# jit_pcb_smd.net
KiCad netlist of a schematic drawn in EAGLE
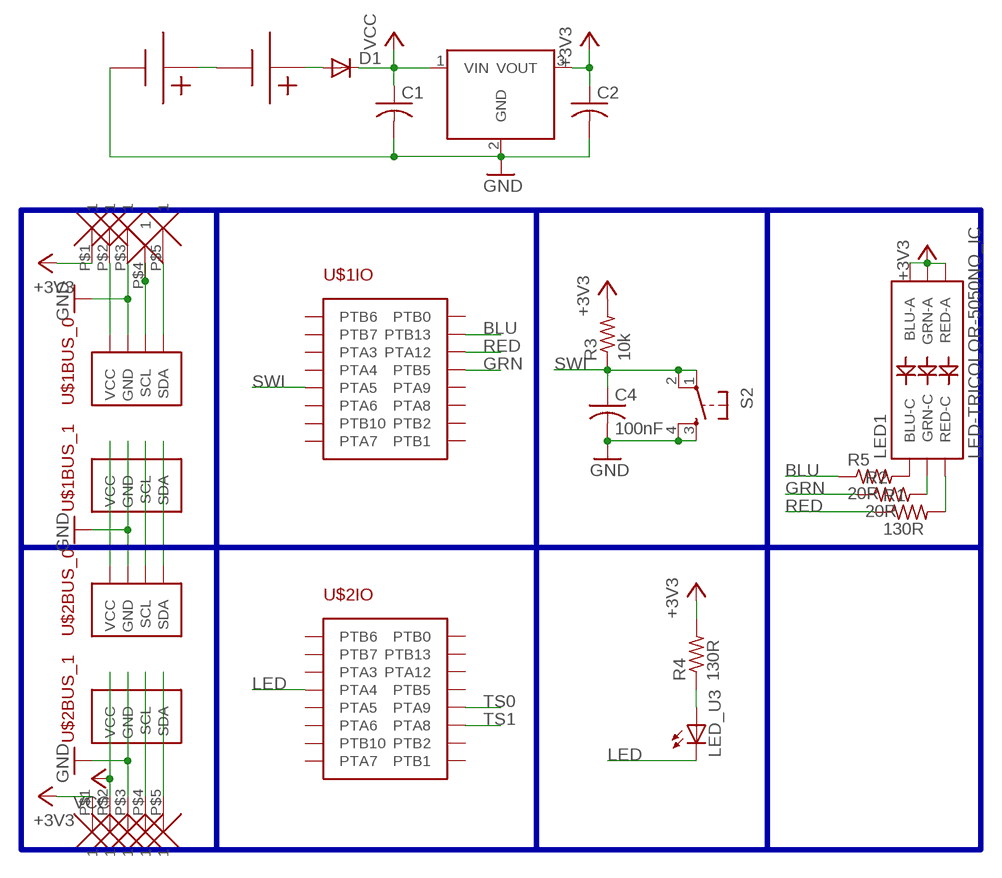
[diagram p0: schematic, sheet 1]

(export (version "E")
  (design (tool "Eeschema 10.0.6"))
  (components
    (comp (ref "C1")
      (value "C-USC0805")
      (footprint "eagle-import:C0805")
      (libsource (lib "eagle-import") (part "C-USC0805"))
    )
    (comp (ref "C2")
      (value "C-USC0805")
      (footprint "eagle-import:C0805")
      (libsource (lib "eagle-import") (part "C-USC0805"))
    )
    (comp (ref "C4")
      (value "100nF")
      (footprint "eagle-import:C0805")
      (libsource (lib "eagle-import") (part "C-USC0805"))
    )
    (comp (ref "D1")
      (value "DIODE-SMC")
      (footprint "eagle-import:SMC")
      (libsource (lib "eagle-import") (part "DIODE-SMC"))
    )
    (comp (ref "LED1")
      (value "LED-TRICOLOR-5050NO_IC")
      (footprint "eagle-import:LED-TRICOLOR-5050")
      (libsource (lib "eagle-import") (part "LED-TRICOLOR-5050NO_IC"))
    )
    (comp (ref "LED_U3")
      (value "LEDCHIP-LED0805")
      (footprint "eagle-import:CHIP-LED0805")
      (libsource (lib "eagle-import") (part "LEDCHIP-LED0805"))
    )
    (comp (ref "R1")
      (value "130R")
      (footprint "eagle-import:R0805")
      (libsource (lib "eagle-import") (part "R-US_R0805"))
    )
    (comp (ref "R2")
      (value "20R")
      (footprint "eagle-import:R0805")
      (libsource (lib "eagle-import") (part "R-US_R0805"))
    )
    (comp (ref "R3")
      (value "10k")
      (footprint "eagle-import:R0805")
      (libsource (lib "eagle-import") (part "R-US_R0805"))
    )
    (comp (ref "R4")
      (value "130R")
      (footprint "eagle-import:R0805")
      (libsource (lib "eagle-import") (part "R-US_R0805"))
    )
    (comp (ref "R5")
      (value "20R")
      (footprint "eagle-import:R0805")
      (libsource (lib "eagle-import") (part "R-US_R0805"))
    )
    (comp (ref "S2")
      (value "TAC_SWITCHSMD")
      (footprint "eagle-import:TACTILE_SWITCH_SMD")
      (libsource (lib "eagle-import") (part "TAC_SWITCHSMD"))
    )
    (comp (ref "U$1")
      (value "MODROB_CARRIER-SMD")
      (footprint "eagle-import:CARRIER_SMD")
      (libsource (lib "eagle-import") (part "MODROB_CARRIER-SMD"))
    )
    (comp (ref "U$2")
      (value "MODROB_CARRIER-SMD")
      (footprint "eagle-import:CARRIER_SMD")
      (libsource (lib "eagle-import") (part "MODROB_CARRIER-SMD"))
    )
    (comp (ref "U$3")
      (value "CR3023")
      (footprint "eagle-import:BU2032SM-G")
      (libsource (lib "eagle-import") (part "CR3023"))
    )
    (comp (ref "U$4")
      (value "CR3023")
      (footprint "eagle-import:BU2032SM-G")
      (libsource (lib "eagle-import") (part "CR3023"))
    )
    (comp (ref "U$5")
      (value "TC1262")
      (footprint "eagle-import:SOT223")
      (libsource (lib "eagle-import") (part "TC1262"))
    )
    (comp (ref "U$6")
      (value "1X5_SMD")
      (footprint "eagle-import:1X5_SMD")
      (libsource (lib "eagle-import") (part "1X5_SMD"))
    )
    (comp (ref "U$7")
      (value "1X5_SMD")
      (footprint "eagle-import:1X5_SMD")
      (libsource (lib "eagle-import") (part "1X5_SMD"))
    )
  )
  (nets
    (net (code "1") (name "+3V3") (class "Default")
      (node (ref "C2") (pin "1") (pinfunction "1_1") (pintype "passive"))
      (node (ref "LED1") (pin "1") (pinfunction "GRN-A_1") (pintype "bidirectional"))
      (node (ref "LED1") (pin "2") (pinfunction "RED-A_2") (pintype "bidirectional"))
      (node (ref "LED1") (pin "3") (pinfunction "BLU-A_3") (pintype "bidirectional"))
      (node (ref "R3") (pin "2") (pinfunction "2_2") (pintype "passive"))
      (node (ref "R4") (pin "2") (pinfunction "2_2") (pintype "passive"))
      (node (ref "U$5") (pin "3") (pinfunction "VOUT_3") (pintype "bidirectional"))
      (node (ref "U$6") (pin "P$1") (pinfunction "1_P$1") (pintype "bidirectional"))
      (node (ref "U$7") (pin "P$1") (pinfunction "1_P$1") (pintype "bidirectional"))
    )
    (net (code "2") (name "/BLU") (class "Default")
      (node (ref "R5") (pin "1") (pinfunction "1_1") (pintype "passive"))
      (node (ref "U$1") (pin "PTB13") (pinfunction "PTB13_PTB13") (pintype "bidirectional"))
    )
    (net (code "3") (name "/GRN") (class "Default")
      (node (ref "R2") (pin "1") (pinfunction "1_1") (pintype "passive"))
      (node (ref "U$1") (pin "PTB5") (pinfunction "PTB5_PTB5") (pintype "bidirectional"))
    )
    (net (code "4") (name "/LED") (class "Default")
      (node (ref "LED_U3") (pin "C") (pinfunction "C_C") (pintype "passive"))
      (node (ref "U$2") (pin "PTA4") (pinfunction "PTA4_PTA4") (pintype "bidirectional"))
    )
    (net (code "5") (name "/RED") (class "Default")
      (node (ref "R1") (pin "1") (pinfunction "1_1") (pintype "passive"))
      (node (ref "U$1") (pin "PTA12") (pinfunction "PTA12_PTA12") (pintype "bidirectional"))
    )
    (net (code "6") (name "/SWI") (class "Default")
      (node (ref "C4") (pin "1") (pinfunction "1_1") (pintype "passive"))
      (node (ref "R3") (pin "1") (pinfunction "1_1") (pintype "passive"))
      (node (ref "S2") (pin "1") (pinfunction "1_1") (pintype "passive"))
      (node (ref "S2") (pin "2") (pinfunction "2_2") (pintype "passive"))
      (node (ref "U$1") (pin "PTA5") (pinfunction "PTA5_PTA5") (pintype "bidirectional"))
    )
    (net (code "7") (name "/TS0") (class "Default")
      (node (ref "U$2") (pin "PTA9") (pinfunction "PTA9_PTA9") (pintype "bidirectional"))
    )
    (net (code "8") (name "/TS1") (class "Default")
      (node (ref "U$2") (pin "PTA8") (pinfunction "PTA8_PTA8") (pintype "bidirectional"))
    )
    (net (code "9") (name "GND") (class "Default")
      (node (ref "C1") (pin "2") (pinfunction "2_2") (pintype "passive"))
      (node (ref "C2") (pin "2") (pinfunction "2_2") (pintype "passive"))
      (node (ref "C4") (pin "2") (pinfunction "2_2") (pintype "passive"))
      (node (ref "S2") (pin "3") (pinfunction "3_3") (pintype "passive"))
      (node (ref "S2") (pin "4") (pinfunction "4_4") (pintype "passive"))
      (node (ref "U$1") (pin "GND_0") (pinfunction "GND_GND_0") (pintype "bidirectional"))
      (node (ref "U$1") (pin "GND_1") (pinfunction "GND_GND_1") (pintype "bidirectional"))
      (node (ref "U$2") (pin "GND_0") (pinfunction "GND_GND_0") (pintype "bidirectional"))
      (node (ref "U$2") (pin "GND_1") (pinfunction "GND_GND_1") (pintype "bidirectional"))
      (node (ref "U$3") (pin "-") (pinfunction "-_-") (pintype "bidirectional"))
      (node (ref "U$5") (pin "2") (pinfunction "GND_2") (pintype "bidirectional"))
      (node (ref "U$6") (pin "P$3") (pinfunction "1_P$3") (pintype "bidirectional"))
      (node (ref "U$7") (pin "P$3") (pinfunction "1_P$3") (pintype "bidirectional"))
    )
    (net (code "10") (name "Net-(D1-PadA)") (class "Default")
      (node (ref "D1") (pin "A") (pinfunction "A_A") (pintype "passive"))
      (node (ref "U$4") (pin "+") (pinfunction "+_+") (pintype "bidirectional"))
    )
    (net (code "11") (name "Net-(LED1-BLU-C)") (class "Default")
      (node (ref "LED1") (pin "4") (pinfunction "BLU-C_4") (pintype "bidirectional"))
      (node (ref "R5") (pin "2") (pinfunction "2_2") (pintype "passive"))
    )
    (net (code "12") (name "Net-(LED1-GRN-C)") (class "Default")
      (node (ref "LED1") (pin "6") (pinfunction "GRN-C_6") (pintype "bidirectional"))
      (node (ref "R2") (pin "2") (pinfunction "2_2") (pintype "passive"))
    )
    (net (code "13") (name "Net-(LED1-RED-C)") (class "Default")
      (node (ref "LED1") (pin "5") (pinfunction "RED-C_5") (pintype "bidirectional"))
      (node (ref "R1") (pin "2") (pinfunction "2_2") (pintype "passive"))
    )
    (net (code "14") (name "Net-(LED_U3-PadA)") (class "Default")
      (node (ref "LED_U3") (pin "A") (pinfunction "A_A") (pintype "passive"))
      (node (ref "R4") (pin "1") (pinfunction "1_1") (pintype "passive"))
    )
    (net (code "15") (name "Net-(U$1A-SCL)") (class "Default")
      (node (ref "U$1") (pin "SCL_0") (pinfunction "SCL_SCL_0") (pintype "bidirectional"))
      (node (ref "U$7") (pin "P$4") (pinfunction "1_P$4") (pintype "bidirectional"))
    )
    (net (code "16") (name "Net-(U$1A-SDA)") (class "Default")
      (node (ref "U$1") (pin "SDA_0") (pinfunction "SDA_SDA_0") (pintype "bidirectional"))
      (node (ref "U$7") (pin "P$5") (pinfunction "1_P$5") (pintype "bidirectional"))
    )
    (net (code "17") (name "Net-(U$1A-VCC)") (class "Default")
      (node (ref "U$1") (pin "VCC_0") (pinfunction "VCC_VCC_0") (pintype "bidirectional"))
      (node (ref "U$7") (pin "P$2") (pinfunction "1_P$2") (pintype "bidirectional"))
    )
    (net (code "18") (name "Net-(U$1B-SCL)") (class "Default")
      (node (ref "U$1") (pin "SCL_1") (pinfunction "SCL_SCL_1") (pintype "bidirectional"))
      (node (ref "U$2") (pin "SCL_0") (pinfunction "SCL_SCL_0") (pintype "bidirectional"))
    )
    (net (code "19") (name "Net-(U$1B-SDA)") (class "Default")
      (node (ref "U$1") (pin "SDA_1") (pinfunction "SDA_SDA_1") (pintype "bidirectional"))
      (node (ref "U$2") (pin "SDA_0") (pinfunction "SDA_SDA_0") (pintype "bidirectional"))
    )
    (net (code "20") (name "Net-(U$1B-VCC)") (class "Default")
      (node (ref "U$1") (pin "VCC_1") (pinfunction "VCC_VCC_1") (pintype "bidirectional"))
      (node (ref "U$2") (pin "VCC_0") (pinfunction "VCC_VCC_0") (pintype "bidirectional"))
    )
    (net (code "21") (name "Net-(U$2B-SCL)") (class "Default")
      (node (ref "U$2") (pin "SCL_1") (pinfunction "SCL_SCL_1") (pintype "bidirectional"))
      (node (ref "U$6") (pin "P$4") (pinfunction "1_P$4") (pintype "bidirectional"))
    )
    (net (code "22") (name "Net-(U$2B-SDA)") (class "Default")
      (node (ref "U$2") (pin "SDA_1") (pinfunction "SDA_SDA_1") (pintype "bidirectional"))
      (node (ref "U$6") (pin "P$5") (pinfunction "1_P$5") (pintype "bidirectional"))
    )
    (net (code "23") (name "Net-(U$3-Pad+)") (class "Default")
      (node (ref "U$3") (pin "+") (pinfunction "+_+") (pintype "bidirectional"))
      (node (ref "U$4") (pin "-") (pinfunction "-_-") (pintype "bidirectional"))
    )
    (net (code "24") (name "VCC") (class "Default")
      (node (ref "C1") (pin "1") (pinfunction "1_1") (pintype "passive"))
      (node (ref "D1") (pin "C") (pinfunction "C_C") (pintype "passive"))
      (node (ref "U$2") (pin "VCC_1") (pinfunction "VCC_VCC_1") (pintype "bidirectional"))
      (node (ref "U$5") (pin "1") (pinfunction "VIN_1") (pintype "bidirectional"))
      (node (ref "U$6") (pin "P$2") (pinfunction "1_P$2") (pintype "bidirectional"))
    )
    (net (code "25") (name "unconnected-(U$1-PadPTA3)") (class "Default")
      (node (ref "U$1") (pin "PTA3") (pinfunction "PTA3_PTA3") (pintype "bidirectional"))
    )
    (net (code "26") (name "unconnected-(U$1-PadPTA4)") (class "Default")
      (node (ref "U$1") (pin "PTA4") (pinfunction "PTA4_PTA4") (pintype "bidirectional"))
    )
    (net (code "27") (name "unconnected-(U$1-PadPTA6)") (class "Default")
      (node (ref "U$1") (pin "PTA6") (pinfunction "PTA6_PTA6") (pintype "bidirectional"))
    )
    (net (code "28") (name "unconnected-(U$1-PadPTA7)") (class "Default")
      (node (ref "U$1") (pin "PTA7") (pinfunction "PTA7_PTA7") (pintype "bidirectional"))
    )
    (net (code "29") (name "unconnected-(U$1-PadPTA8)") (class "Default")
      (node (ref "U$1") (pin "PTA8") (pinfunction "PTA8_PTA8") (pintype "bidirectional"))
    )
    (net (code "30") (name "unconnected-(U$1-PadPTA9)") (class "Default")
      (node (ref "U$1") (pin "PTA9") (pinfunction "PTA9_PTA9") (pintype "bidirectional"))
    )
    (net (code "31") (name "unconnected-(U$1-PadPTB0)") (class "Default")
      (node (ref "U$1") (pin "PTB0") (pinfunction "PTB0_PTB0") (pintype "bidirectional"))
    )
    (net (code "32") (name "unconnected-(U$1-PadPTB1)") (class "Default")
      (node (ref "U$1") (pin "PTB1") (pinfunction "PTB1_PTB1") (pintype "bidirectional"))
    )
    (net (code "33") (name "unconnected-(U$1-PadPTB2)") (class "Default")
      (node (ref "U$1") (pin "PTB2") (pinfunction "PTB2_PTB2") (pintype "bidirectional"))
    )
    (net (code "34") (name "unconnected-(U$1-PadPTB6)") (class "Default")
      (node (ref "U$1") (pin "PTB6") (pinfunction "PTB6_PTB6") (pintype "bidirectional"))
    )
    (net (code "35") (name "unconnected-(U$1-PadPTB7)") (class "Default")
      (node (ref "U$1") (pin "PTB7") (pinfunction "PTB7_PTB7") (pintype "bidirectional"))
    )
    (net (code "36") (name "unconnected-(U$1-PadPTB10)") (class "Default")
      (node (ref "U$1") (pin "PTB10") (pinfunction "PTB10_PTB10") (pintype "bidirectional"))
    )
    (net (code "37") (name "unconnected-(U$2-PadPTA3)") (class "Default")
      (node (ref "U$2") (pin "PTA3") (pinfunction "PTA3_PTA3") (pintype "bidirectional"))
    )
    (net (code "38") (name "unconnected-(U$2-PadPTA5)") (class "Default")
      (node (ref "U$2") (pin "PTA5") (pinfunction "PTA5_PTA5") (pintype "bidirectional"))
    )
    (net (code "39") (name "unconnected-(U$2-PadPTA6)") (class "Default")
      (node (ref "U$2") (pin "PTA6") (pinfunction "PTA6_PTA6") (pintype "bidirectional"))
    )
    (net (code "40") (name "unconnected-(U$2-PadPTA7)") (class "Default")
      (node (ref "U$2") (pin "PTA7") (pinfunction "PTA7_PTA7") (pintype "bidirectional"))
    )
    (net (code "41") (name "unconnected-(U$2-PadPTA12)") (class "Default")
      (node (ref "U$2") (pin "PTA12") (pinfunction "PTA12_PTA12") (pintype "bidirectional"))
    )
    (net (code "42") (name "unconnected-(U$2-PadPTB0)") (class "Default")
      (node (ref "U$2") (pin "PTB0") (pinfunction "PTB0_PTB0") (pintype "bidirectional"))
    )
    (net (code "43") (name "unconnected-(U$2-PadPTB1)") (class "Default")
      (node (ref "U$2") (pin "PTB1") (pinfunction "PTB1_PTB1") (pintype "bidirectional"))
    )
    (net (code "44") (name "unconnected-(U$2-PadPTB2)") (class "Default")
      (node (ref "U$2") (pin "PTB2") (pinfunction "PTB2_PTB2") (pintype "bidirectional"))
    )
    (net (code "45") (name "unconnected-(U$2-PadPTB5)") (class "Default")
      (node (ref "U$2") (pin "PTB5") (pinfunction "PTB5_PTB5") (pintype "bidirectional"))
    )
    (net (code "46") (name "unconnected-(U$2-PadPTB6)") (class "Default")
      (node (ref "U$2") (pin "PTB6") (pinfunction "PTB6_PTB6") (pintype "bidirectional"))
    )
    (net (code "47") (name "unconnected-(U$2-PadPTB7)") (class "Default")
      (node (ref "U$2") (pin "PTB7") (pinfunction "PTB7_PTB7") (pintype "bidirectional"))
    )
    (net (code "48") (name "unconnected-(U$2-PadPTB10)") (class "Default")
      (node (ref "U$2") (pin "PTB10") (pinfunction "PTB10_PTB10") (pintype "bidirectional"))
    )
    (net (code "49") (name "unconnected-(U$2-PadPTB13)") (class "Default")
      (node (ref "U$2") (pin "PTB13") (pinfunction "PTB13_PTB13") (pintype "bidirectional"))
    )
  )
)
